# TinyCharlieCylon.net
KiCad netlist of a schematic drawn in EAGLE
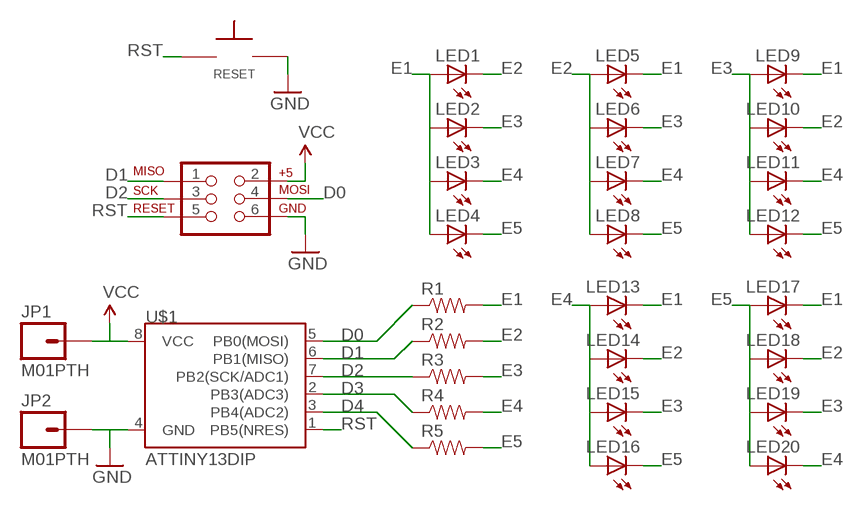
[diagram p0: schematic, sheet 1]

(export (version "E")
  (design (tool "Eeschema 10.0.6"))
  (components
    (comp (ref "J1")
      (value "AVR_SPI_PRG_6PTH")
      (footprint "eagle-import:2X3")
      (libsource (lib "eagle-import") (part "AVR_SPI_PRG_6PTH"))
    )
    (comp (ref "JP1")
      (value "M01PTH")
      (footprint "eagle-import:1X01")
      (libsource (lib "eagle-import") (part "M01PTH"))
    )
    (comp (ref "JP2")
      (value "M01PTH")
      (footprint "eagle-import:1X01")
      (libsource (lib "eagle-import") (part "M01PTH"))
    )
    (comp (ref "LED1")
      (value "LED3MM")
      (footprint "eagle-import:LED3MM")
      (libsource (lib "eagle-import") (part "LED3MM"))
    )
    (comp (ref "LED2")
      (value "LED3MM")
      (footprint "eagle-import:LED3MM")
      (libsource (lib "eagle-import") (part "LED3MM"))
    )
    (comp (ref "LED3")
      (value "LED3MM")
      (footprint "eagle-import:LED3MM")
      (libsource (lib "eagle-import") (part "LED3MM"))
    )
    (comp (ref "LED4")
      (value "LED3MM")
      (footprint "eagle-import:LED3MM")
      (libsource (lib "eagle-import") (part "LED3MM"))
    )
    (comp (ref "LED5")
      (value "LED3MM")
      (footprint "eagle-import:LED3MM")
      (libsource (lib "eagle-import") (part "LED3MM"))
    )
    (comp (ref "LED6")
      (value "LED3MM")
      (footprint "eagle-import:LED3MM")
      (libsource (lib "eagle-import") (part "LED3MM"))
    )
    (comp (ref "LED7")
      (value "LED3MM")
      (footprint "eagle-import:LED3MM")
      (libsource (lib "eagle-import") (part "LED3MM"))
    )
    (comp (ref "LED8")
      (value "LED3MM")
      (footprint "eagle-import:LED3MM")
      (libsource (lib "eagle-import") (part "LED3MM"))
    )
    (comp (ref "LED9")
      (value "LED3MM")
      (footprint "eagle-import:LED3MM")
      (libsource (lib "eagle-import") (part "LED3MM"))
    )
    (comp (ref "LED10")
      (value "LED3MM")
      (footprint "eagle-import:LED3MM")
      (libsource (lib "eagle-import") (part "LED3MM"))
    )
    (comp (ref "LED11")
      (value "LED3MM")
      (footprint "eagle-import:LED3MM")
      (libsource (lib "eagle-import") (part "LED3MM"))
    )
    (comp (ref "LED12")
      (value "LED3MM")
      (footprint "eagle-import:LED3MM")
      (libsource (lib "eagle-import") (part "LED3MM"))
    )
    (comp (ref "LED13")
      (value "LED3MM")
      (footprint "eagle-import:LED3MM")
      (libsource (lib "eagle-import") (part "LED3MM"))
    )
    (comp (ref "LED14")
      (value "LED3MM")
      (footprint "eagle-import:LED3MM")
      (libsource (lib "eagle-import") (part "LED3MM"))
    )
    (comp (ref "LED15")
      (value "LED3MM")
      (footprint "eagle-import:LED3MM")
      (libsource (lib "eagle-import") (part "LED3MM"))
    )
    (comp (ref "LED16")
      (value "LED3MM")
      (footprint "eagle-import:LED3MM")
      (libsource (lib "eagle-import") (part "LED3MM"))
    )
    (comp (ref "LED17")
      (value "LED3MM")
      (footprint "eagle-import:LED3MM")
      (libsource (lib "eagle-import") (part "LED3MM"))
    )
    (comp (ref "LED18")
      (value "LED3MM")
      (footprint "eagle-import:LED3MM")
      (libsource (lib "eagle-import") (part "LED3MM"))
    )
    (comp (ref "LED19")
      (value "LED3MM")
      (footprint "eagle-import:LED3MM")
      (libsource (lib "eagle-import") (part "LED3MM"))
    )
    (comp (ref "LED20")
      (value "LED3MM")
      (footprint "eagle-import:LED3MM")
      (libsource (lib "eagle-import") (part "LED3MM"))
    )
    (comp (ref "R1")
      (value "RESISTORAXIAL-0.3")
      (footprint "eagle-import:AXIAL-0.3")
      (libsource (lib "eagle-import") (part "RESISTORAXIAL-0.3"))
    )
    (comp (ref "R2")
      (value "RESISTORAXIAL-0.3")
      (footprint "eagle-import:AXIAL-0.3")
      (libsource (lib "eagle-import") (part "RESISTORAXIAL-0.3"))
    )
    (comp (ref "R3")
      (value "RESISTORAXIAL-0.3")
      (footprint "eagle-import:AXIAL-0.3")
      (libsource (lib "eagle-import") (part "RESISTORAXIAL-0.3"))
    )
    (comp (ref "R4")
      (value "RESISTORAXIAL-0.3")
      (footprint "eagle-import:AXIAL-0.3")
      (libsource (lib "eagle-import") (part "RESISTORAXIAL-0.3"))
    )
    (comp (ref "R5")
      (value "RESISTORAXIAL-0.3")
      (footprint "eagle-import:AXIAL-0.3")
      (libsource (lib "eagle-import") (part "RESISTORAXIAL-0.3"))
    )
    (comp (ref "RESET")
      (value "TAC_SPST_NO")
      (footprint "eagle-import:TAC_SPST_NO")
      (libsource (lib "eagle-import") (part "TAC_SPST_NO"))
    )
    (comp (ref "U$1")
      (value "ATTINY13DIP")
      (footprint "eagle-import:DIP08")
      (libsource (lib "eagle-import") (part "ATTINY13DIP"))
    )
  )
  (nets
    (net (code "1") (name "/D0") (class "Default")
      (node (ref "J1") (pin "4") (pinfunction "4_4") (pintype "passive"))
      (node (ref "R1") (pin "P$1") (pinfunction "1_P$1") (pintype "passive"))
      (node (ref "U$1") (pin "5") (pinfunction "PB0(MOSI)_5") (pintype "bidirectional"))
    )
    (net (code "2") (name "/D1") (class "Default")
      (node (ref "J1") (pin "1") (pinfunction "1_1") (pintype "passive"))
      (node (ref "R2") (pin "P$1") (pinfunction "1_P$1") (pintype "passive"))
      (node (ref "U$1") (pin "6") (pinfunction "PB1(MISO)_6") (pintype "bidirectional"))
    )
    (net (code "3") (name "/D2") (class "Default")
      (node (ref "J1") (pin "3") (pinfunction "3_3") (pintype "passive"))
      (node (ref "R3") (pin "P$1") (pinfunction "1_P$1") (pintype "passive"))
      (node (ref "U$1") (pin "7") (pinfunction "PB2(SCK/ADC1)_7") (pintype "bidirectional"))
    )
    (net (code "4") (name "/D3") (class "Default")
      (node (ref "R4") (pin "P$1") (pinfunction "1_P$1") (pintype "passive"))
      (node (ref "U$1") (pin "2") (pinfunction "PB3(ADC3)_2") (pintype "bidirectional"))
    )
    (net (code "5") (name "/D4") (class "Default")
      (node (ref "R5") (pin "P$1") (pinfunction "1_P$1") (pintype "passive"))
      (node (ref "U$1") (pin "3") (pinfunction "PB4(ADC2)_3") (pintype "bidirectional"))
    )
    (net (code "6") (name "/E1") (class "Default")
      (node (ref "LED1") (pin "A") (pinfunction "A_A") (pintype "passive"))
      (node (ref "LED13") (pin "K") (pinfunction "C_K") (pintype "passive"))
      (node (ref "LED17") (pin "K") (pinfunction "C_K") (pintype "passive"))
      (node (ref "LED2") (pin "A") (pinfunction "A_A") (pintype "passive"))
      (node (ref "LED3") (pin "A") (pinfunction "A_A") (pintype "passive"))
      (node (ref "LED4") (pin "A") (pinfunction "A_A") (pintype "passive"))
      (node (ref "LED5") (pin "K") (pinfunction "C_K") (pintype "passive"))
      (node (ref "LED9") (pin "K") (pinfunction "C_K") (pintype "passive"))
      (node (ref "R1") (pin "P$2") (pinfunction "2_P$2") (pintype "passive"))
    )
    (net (code "7") (name "/E2") (class "Default")
      (node (ref "LED1") (pin "K") (pinfunction "C_K") (pintype "passive"))
      (node (ref "LED10") (pin "K") (pinfunction "C_K") (pintype "passive"))
      (node (ref "LED14") (pin "K") (pinfunction "C_K") (pintype "passive"))
      (node (ref "LED18") (pin "K") (pinfunction "C_K") (pintype "passive"))
      (node (ref "LED5") (pin "A") (pinfunction "A_A") (pintype "passive"))
      (node (ref "LED6") (pin "A") (pinfunction "A_A") (pintype "passive"))
      (node (ref "LED7") (pin "A") (pinfunction "A_A") (pintype "passive"))
      (node (ref "LED8") (pin "A") (pinfunction "A_A") (pintype "passive"))
      (node (ref "R2") (pin "P$2") (pinfunction "2_P$2") (pintype "passive"))
    )
    (net (code "8") (name "/E3") (class "Default")
      (node (ref "LED10") (pin "A") (pinfunction "A_A") (pintype "passive"))
      (node (ref "LED11") (pin "A") (pinfunction "A_A") (pintype "passive"))
      (node (ref "LED12") (pin "A") (pinfunction "A_A") (pintype "passive"))
      (node (ref "LED15") (pin "K") (pinfunction "C_K") (pintype "passive"))
      (node (ref "LED19") (pin "K") (pinfunction "C_K") (pintype "passive"))
      (node (ref "LED2") (pin "K") (pinfunction "C_K") (pintype "passive"))
      (node (ref "LED6") (pin "K") (pinfunction "C_K") (pintype "passive"))
      (node (ref "LED9") (pin "A") (pinfunction "A_A") (pintype "passive"))
      (node (ref "R3") (pin "P$2") (pinfunction "2_P$2") (pintype "passive"))
    )
    (net (code "9") (name "/E4") (class "Default")
      (node (ref "LED11") (pin "K") (pinfunction "C_K") (pintype "passive"))
      (node (ref "LED13") (pin "A") (pinfunction "A_A") (pintype "passive"))
      (node (ref "LED14") (pin "A") (pinfunction "A_A") (pintype "passive"))
      (node (ref "LED15") (pin "A") (pinfunction "A_A") (pintype "passive"))
      (node (ref "LED16") (pin "A") (pinfunction "A_A") (pintype "passive"))
      (node (ref "LED20") (pin "K") (pinfunction "C_K") (pintype "passive"))
      (node (ref "LED3") (pin "K") (pinfunction "C_K") (pintype "passive"))
      (node (ref "LED7") (pin "K") (pinfunction "C_K") (pintype "passive"))
      (node (ref "R4") (pin "P$2") (pinfunction "2_P$2") (pintype "passive"))
    )
    (net (code "10") (name "/E5") (class "Default")
      (node (ref "LED12") (pin "K") (pinfunction "C_K") (pintype "passive"))
      (node (ref "LED16") (pin "K") (pinfunction "C_K") (pintype "passive"))
      (node (ref "LED17") (pin "A") (pinfunction "A_A") (pintype "passive"))
      (node (ref "LED18") (pin "A") (pinfunction "A_A") (pintype "passive"))
      (node (ref "LED19") (pin "A") (pinfunction "A_A") (pintype "passive"))
      (node (ref "LED20") (pin "A") (pinfunction "A_A") (pintype "passive"))
      (node (ref "LED4") (pin "K") (pinfunction "C_K") (pintype "passive"))
      (node (ref "LED8") (pin "K") (pinfunction "C_K") (pintype "passive"))
      (node (ref "R5") (pin "P$2") (pinfunction "2_P$2") (pintype "passive"))
    )
    (net (code "11") (name "/RST") (class "Default")
      (node (ref "J1") (pin "5") (pinfunction "5_5") (pintype "passive"))
      (node (ref "RESET") (pin "P$1") (pinfunction "P$1_P$1") (pintype "bidirectional"))
      (node (ref "U$1") (pin "1") (pinfunction "PB5(NRES)_1") (pintype "bidirectional"))
    )
    (net (code "12") (name "GND") (class "Default")
      (node (ref "J1") (pin "6") (pinfunction "6_6") (pintype "passive"))
      (node (ref "JP2") (pin "1") (pinfunction "1_1") (pintype "passive"))
      (node (ref "RESET") (pin "P$2") (pinfunction "P$2_P$2") (pintype "bidirectional"))
      (node (ref "U$1") (pin "4") (pinfunction "GND_4") (pintype "bidirectional"))
    )
    (net (code "13") (name "VCC") (class "Default")
      (node (ref "J1") (pin "2") (pinfunction "2_2") (pintype "passive"))
      (node (ref "JP1") (pin "1") (pinfunction "1_1") (pintype "passive"))
      (node (ref "U$1") (pin "8") (pinfunction "VCC_8") (pintype "bidirectional"))
    )
  )
)
